# ws2812-cube-reverse.net
KiCad netlist of a schematic drawn in EasyEDA
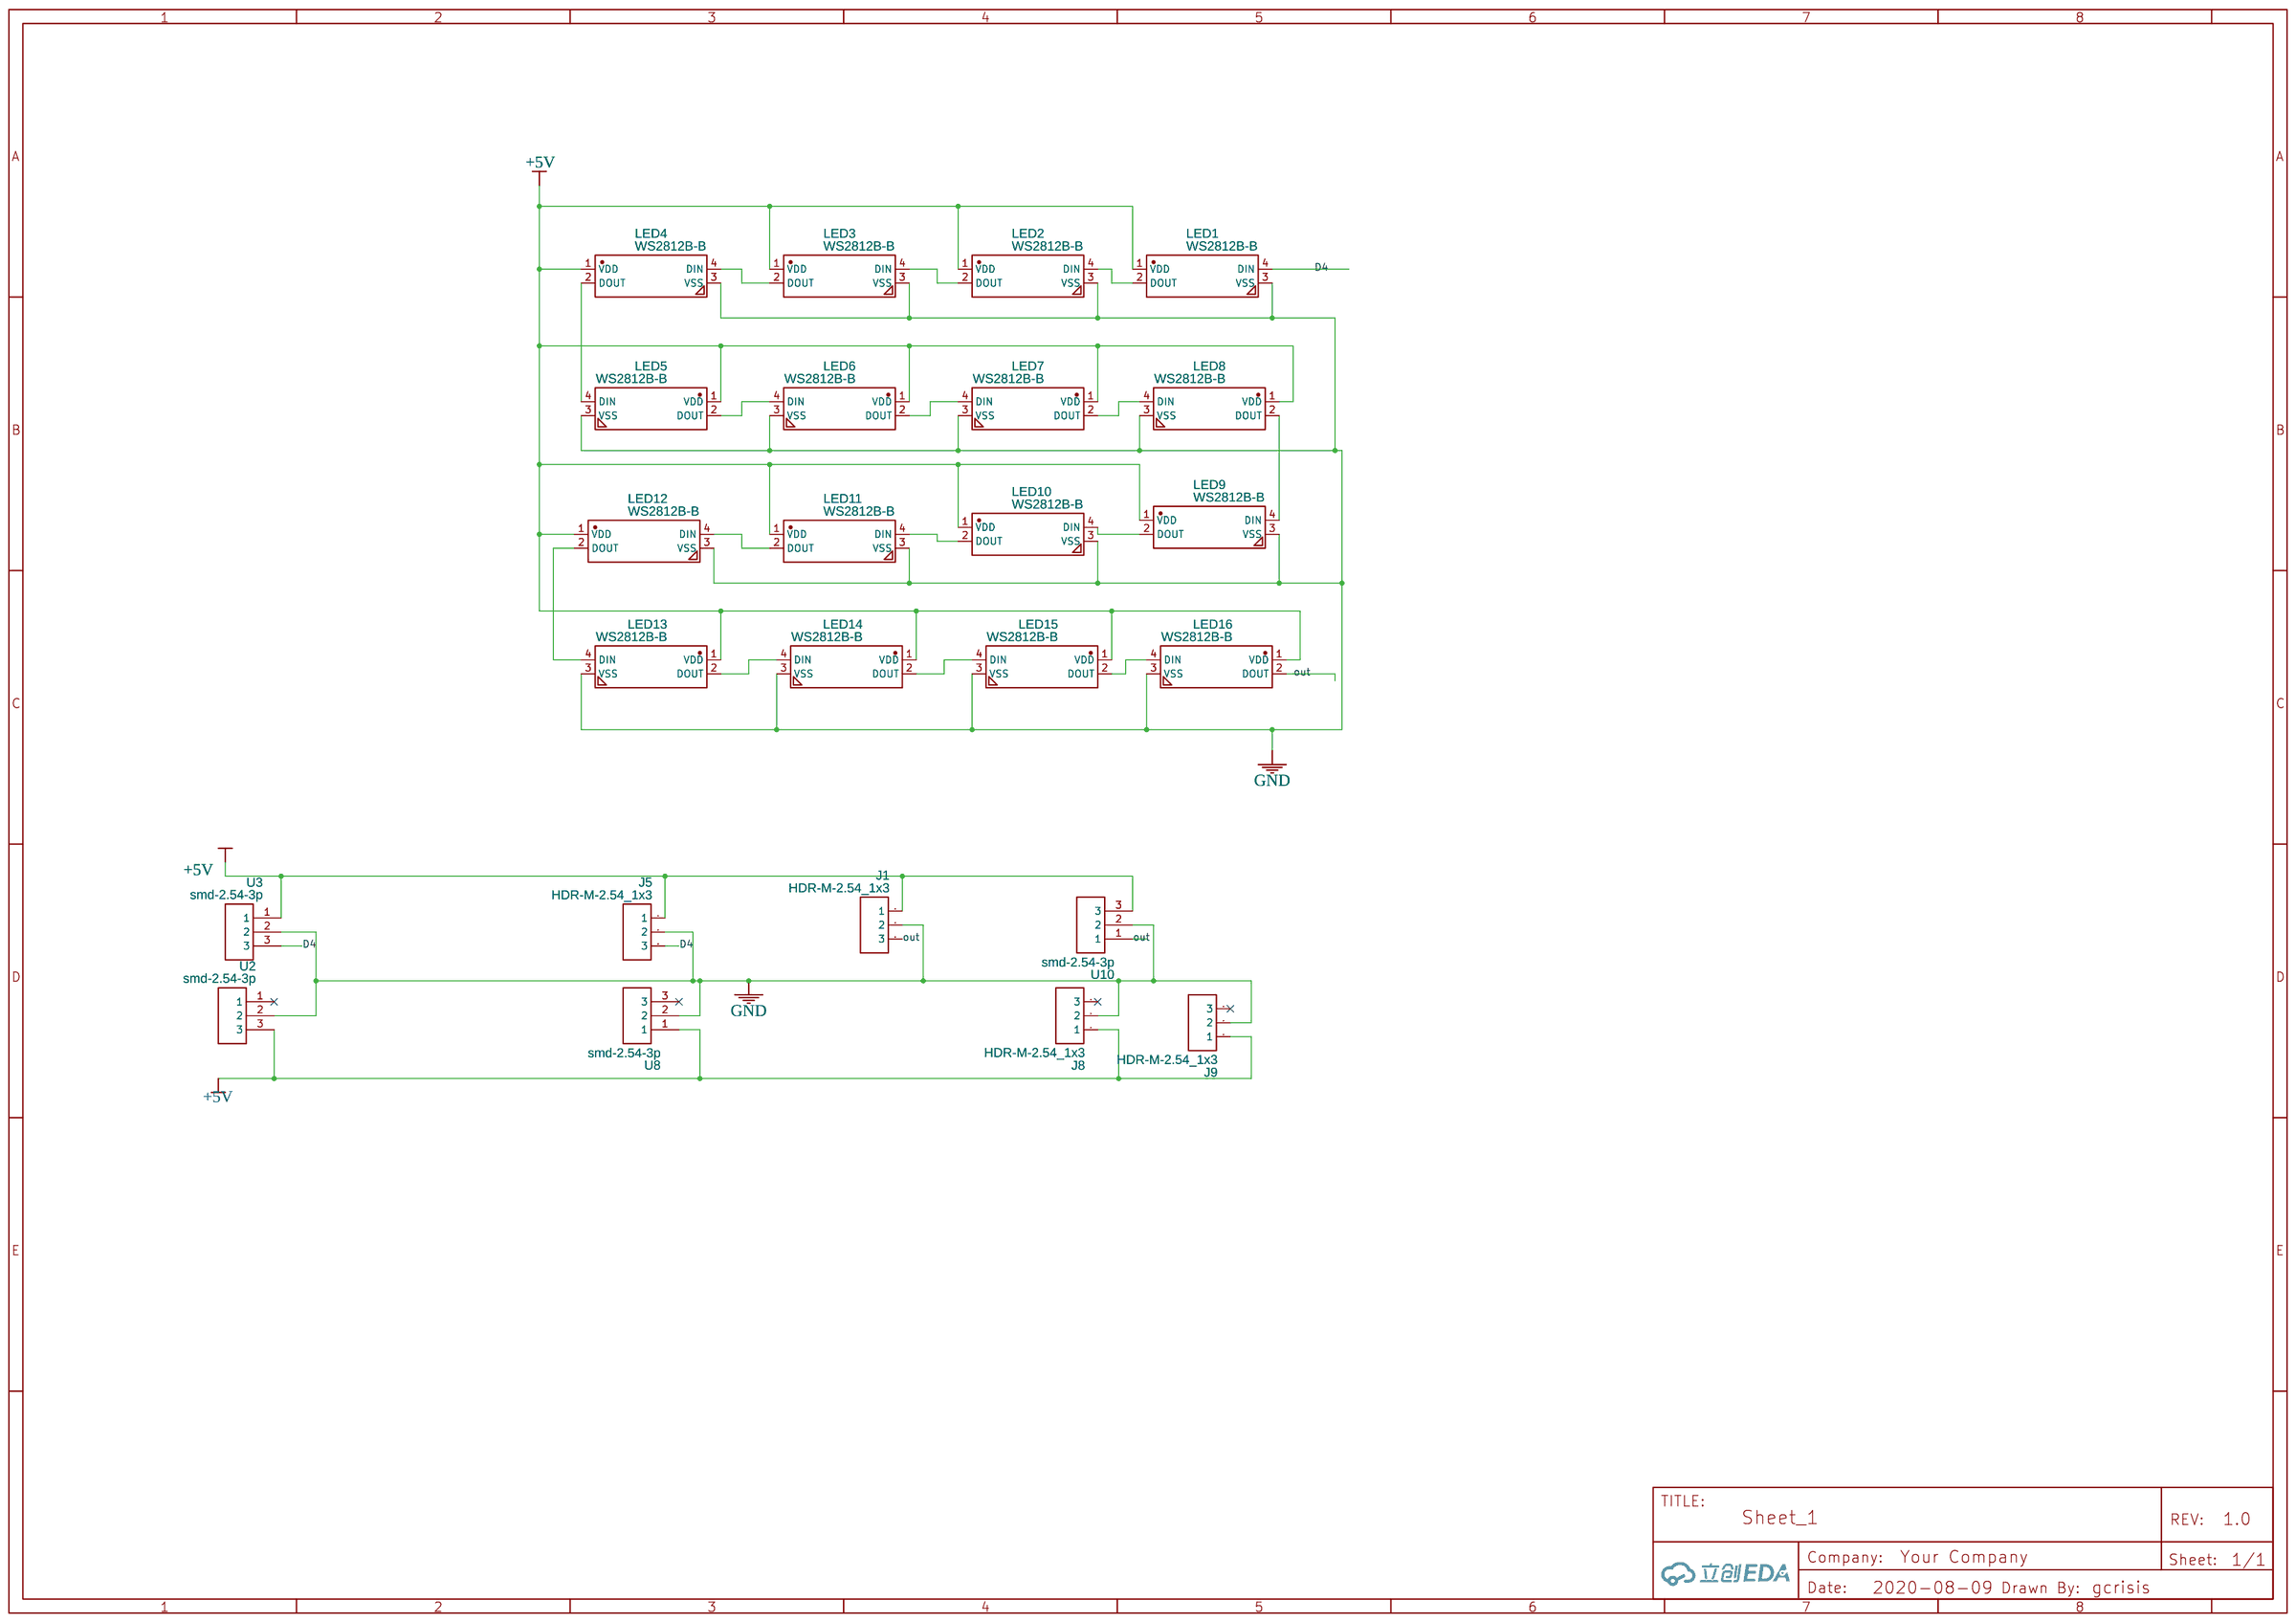
[diagram p0: schematic sheet]

(export (version "E")
  (design (tool "Eeschema 10.0.6"))
  (components
    (comp (ref "J1")
      (value "HDR-M-2.54_1x3")
      (fields (field (name "BOM_Supplier Part") "C180248"))
      (libsource (lib "") (part "HDR-M-2.54_1x3_1"))
    )
    (comp (ref "J5")
      (value "HDR-M-2.54_1x3")
      (fields (field (name "BOM_Supplier Part") "C180248"))
      (libsource (lib "") (part "HDR-M-2.54_1x3_1"))
    )
    (comp (ref "J8")
      (value "HDR-M-2.54_1x3")
      (fields (field (name "BOM_Supplier Part") "C180248"))
      (libsource (lib "") (part "HDR-M-2.54_1x3"))
    )
    (comp (ref "J9")
      (value "HDR-M-2.54_1x3")
      (fields (field (name "BOM_Supplier Part") "C180248"))
      (libsource (lib "") (part "HDR-M-2.54_1x3"))
    )
    (comp (ref "LED1")
      (value "WS2812B-B")
      (fields (field (name "BOM_Supplier Part") "C114586"))
      (libsource (lib "") (part "WS2812B-B"))
    )
    (comp (ref "LED2")
      (value "WS2812B-B")
      (fields (field (name "BOM_Supplier Part") "C114586"))
      (libsource (lib "") (part "WS2812B-B"))
    )
    (comp (ref "LED3")
      (value "WS2812B-B")
      (fields (field (name "BOM_Supplier Part") "C114586"))
      (libsource (lib "") (part "WS2812B-B"))
    )
    (comp (ref "LED4")
      (value "WS2812B-B")
      (fields (field (name "BOM_Supplier Part") "C114586"))
      (libsource (lib "") (part "WS2812B-B"))
    )
    (comp (ref "LED5")
      (value "WS2812B-B")
      (fields (field (name "BOM_Supplier Part") "C114586"))
      (libsource (lib "") (part "WS2812B-B_1"))
    )
    (comp (ref "LED6")
      (value "WS2812B-B")
      (fields (field (name "BOM_Supplier Part") "C114586"))
      (libsource (lib "") (part "WS2812B-B_1"))
    )
    (comp (ref "LED7")
      (value "WS2812B-B")
      (fields (field (name "BOM_Supplier Part") "C114586"))
      (libsource (lib "") (part "WS2812B-B_1"))
    )
    (comp (ref "LED8")
      (value "WS2812B-B")
      (fields (field (name "BOM_Supplier Part") "C114586"))
      (libsource (lib "") (part "WS2812B-B_1"))
    )
    (comp (ref "LED9")
      (value "WS2812B-B")
      (fields (field (name "BOM_Supplier Part") "C114586"))
      (libsource (lib "") (part "WS2812B-B"))
    )
    (comp (ref "LED10")
      (value "WS2812B-B")
      (fields (field (name "BOM_Supplier Part") "C114586"))
      (libsource (lib "") (part "WS2812B-B"))
    )
    (comp (ref "LED11")
      (value "WS2812B-B")
      (fields (field (name "BOM_Supplier Part") "C114586"))
      (libsource (lib "") (part "WS2812B-B"))
    )
    (comp (ref "LED12")
      (value "WS2812B-B")
      (fields (field (name "BOM_Supplier Part") "C114586"))
      (libsource (lib "") (part "WS2812B-B"))
    )
    (comp (ref "LED13")
      (value "WS2812B-B")
      (fields (field (name "BOM_Supplier Part") "C114586"))
      (libsource (lib "") (part "WS2812B-B_1"))
    )
    (comp (ref "LED14")
      (value "WS2812B-B")
      (fields (field (name "BOM_Supplier Part") "C114586"))
      (libsource (lib "") (part "WS2812B-B_1"))
    )
    (comp (ref "LED15")
      (value "WS2812B-B")
      (fields (field (name "BOM_Supplier Part") "C114586"))
      (libsource (lib "") (part "WS2812B-B_1"))
    )
    (comp (ref "LED16")
      (value "WS2812B-B")
      (fields (field (name "BOM_Supplier Part") "C114586"))
      (libsource (lib "") (part "WS2812B-B_1"))
    )
    (comp (ref "U2") (value "smd-2.54-3p") (libsource (lib "") (part "smd-2.54-3p_1")))
    (comp (ref "U3") (value "smd-2.54-3p") (libsource (lib "") (part "smd-2.54-3p_1")))
    (comp (ref "U8") (value "smd-2.54-3p") (libsource (lib "") (part "smd-2.54-3p")))
    (comp (ref "U10") (value "smd-2.54-3p") (libsource (lib "") (part "smd-2.54-3p")))
  )
  (nets
    (net (code "1") (name "+5V") (class "Default")
      (node (ref "J1") (pin "1") (pinfunction "1_1") (pintype "input"))
      (node (ref "J5") (pin "1") (pinfunction "1_1") (pintype "input"))
      (node (ref "J8") (pin "1") (pinfunction "1_1") (pintype "input"))
      (node (ref "J9") (pin "1") (pinfunction "1_1") (pintype "input"))
      (node (ref "LED1") (pin "1") (pinfunction "VDD_1") (pintype "unspecified"))
      (node (ref "LED10") (pin "1") (pinfunction "VDD_1") (pintype "unspecified"))
      (node (ref "LED11") (pin "1") (pinfunction "VDD_1") (pintype "unspecified"))
      (node (ref "LED12") (pin "1") (pinfunction "VDD_1") (pintype "unspecified"))
      (node (ref "LED13") (pin "1") (pinfunction "VDD_1") (pintype "unspecified"))
      (node (ref "LED14") (pin "1") (pinfunction "VDD_1") (pintype "unspecified"))
      (node (ref "LED15") (pin "1") (pinfunction "VDD_1") (pintype "unspecified"))
      (node (ref "LED16") (pin "1") (pinfunction "VDD_1") (pintype "unspecified"))
      (node (ref "LED2") (pin "1") (pinfunction "VDD_1") (pintype "unspecified"))
      (node (ref "LED3") (pin "1") (pinfunction "VDD_1") (pintype "unspecified"))
      (node (ref "LED4") (pin "1") (pinfunction "VDD_1") (pintype "unspecified"))
      (node (ref "LED5") (pin "1") (pinfunction "VDD_1") (pintype "unspecified"))
      (node (ref "LED6") (pin "1") (pinfunction "VDD_1") (pintype "unspecified"))
      (node (ref "LED7") (pin "1") (pinfunction "VDD_1") (pintype "unspecified"))
      (node (ref "LED8") (pin "1") (pinfunction "VDD_1") (pintype "unspecified"))
      (node (ref "LED9") (pin "1") (pinfunction "VDD_1") (pintype "unspecified"))
      (node (ref "U10") (pin "3") (pinfunction "3_3") (pintype "unspecified"))
      (node (ref "U2") (pin "3") (pinfunction "3_3") (pintype "unspecified"))
      (node (ref "U3") (pin "1") (pinfunction "1_1") (pintype "unspecified"))
      (node (ref "U8") (pin "1") (pinfunction "1_1") (pintype "unspecified"))
    )
    (net (code "2") (name "/D4") (class "Default")
      (node (ref "J5") (pin "3") (pinfunction "3_3") (pintype "input"))
      (node (ref "LED1") (pin "4") (pinfunction "DIN_4") (pintype "unspecified"))
      (node (ref "U3") (pin "3") (pinfunction "3_3") (pintype "unspecified"))
    )
    (net (code "3") (name "/out") (class "Default")
      (node (ref "J1") (pin "3") (pinfunction "3_3") (pintype "input"))
      (node (ref "LED16") (pin "2") (pinfunction "DOUT_2") (pintype "unspecified"))
      (node (ref "U10") (pin "1") (pinfunction "1_1") (pintype "unspecified"))
    )
    (net (code "4") (name "GND") (class "Default")
      (node (ref "J1") (pin "2") (pinfunction "2_2") (pintype "input"))
      (node (ref "J5") (pin "2") (pinfunction "2_2") (pintype "input"))
      (node (ref "J8") (pin "2") (pinfunction "2_2") (pintype "input"))
      (node (ref "J9") (pin "2") (pinfunction "2_2") (pintype "input"))
      (node (ref "LED1") (pin "3") (pinfunction "VSS_3") (pintype "unspecified"))
      (node (ref "LED10") (pin "3") (pinfunction "VSS_3") (pintype "unspecified"))
      (node (ref "LED11") (pin "3") (pinfunction "VSS_3") (pintype "unspecified"))
      (node (ref "LED12") (pin "3") (pinfunction "VSS_3") (pintype "unspecified"))
      (node (ref "LED13") (pin "3") (pinfunction "VSS_3") (pintype "unspecified"))
      (node (ref "LED14") (pin "3") (pinfunction "VSS_3") (pintype "unspecified"))
      (node (ref "LED15") (pin "3") (pinfunction "VSS_3") (pintype "unspecified"))
      (node (ref "LED16") (pin "3") (pinfunction "VSS_3") (pintype "unspecified"))
      (node (ref "LED2") (pin "3") (pinfunction "VSS_3") (pintype "unspecified"))
      (node (ref "LED3") (pin "3") (pinfunction "VSS_3") (pintype "unspecified"))
      (node (ref "LED4") (pin "3") (pinfunction "VSS_3") (pintype "unspecified"))
      (node (ref "LED5") (pin "3") (pinfunction "VSS_3") (pintype "unspecified"))
      (node (ref "LED6") (pin "3") (pinfunction "VSS_3") (pintype "unspecified"))
      (node (ref "LED7") (pin "3") (pinfunction "VSS_3") (pintype "unspecified"))
      (node (ref "LED8") (pin "3") (pinfunction "VSS_3") (pintype "unspecified"))
      (node (ref "LED9") (pin "3") (pinfunction "VSS_3") (pintype "unspecified"))
      (node (ref "U10") (pin "2") (pinfunction "2_2") (pintype "unspecified"))
      (node (ref "U2") (pin "2") (pinfunction "2_2") (pintype "unspecified"))
      (node (ref "U3") (pin "2") (pinfunction "2_2") (pintype "unspecified"))
      (node (ref "U8") (pin "2") (pinfunction "2_2") (pintype "unspecified"))
    )
    (net (code "5") (name "Net-(LED1-DOUT)") (class "Default")
      (node (ref "LED1") (pin "2") (pinfunction "DOUT_2") (pintype "unspecified"))
      (node (ref "LED2") (pin "4") (pinfunction "DIN_4") (pintype "unspecified"))
    )
    (net (code "6") (name "Net-(LED2-DOUT)") (class "Default")
      (node (ref "LED2") (pin "2") (pinfunction "DOUT_2") (pintype "unspecified"))
      (node (ref "LED3") (pin "4") (pinfunction "DIN_4") (pintype "unspecified"))
    )
    (net (code "7") (name "Net-(LED3-DOUT)") (class "Default")
      (node (ref "LED3") (pin "2") (pinfunction "DOUT_2") (pintype "unspecified"))
      (node (ref "LED4") (pin "4") (pinfunction "DIN_4") (pintype "unspecified"))
    )
    (net (code "8") (name "Net-(LED4-DOUT)") (class "Default")
      (node (ref "LED4") (pin "2") (pinfunction "DOUT_2") (pintype "unspecified"))
      (node (ref "LED5") (pin "4") (pinfunction "DIN_4") (pintype "unspecified"))
    )
    (net (code "9") (name "Net-(LED5-DOUT)") (class "Default")
      (node (ref "LED5") (pin "2") (pinfunction "DOUT_2") (pintype "unspecified"))
      (node (ref "LED6") (pin "4") (pinfunction "DIN_4") (pintype "unspecified"))
    )
    (net (code "10") (name "Net-(LED6-DOUT)") (class "Default")
      (node (ref "LED6") (pin "2") (pinfunction "DOUT_2") (pintype "unspecified"))
      (node (ref "LED7") (pin "4") (pinfunction "DIN_4") (pintype "unspecified"))
    )
    (net (code "11") (name "Net-(LED7-DOUT)") (class "Default")
      (node (ref "LED7") (pin "2") (pinfunction "DOUT_2") (pintype "unspecified"))
      (node (ref "LED8") (pin "4") (pinfunction "DIN_4") (pintype "unspecified"))
    )
    (net (code "12") (name "Net-(LED8-DOUT)") (class "Default")
      (node (ref "LED8") (pin "2") (pinfunction "DOUT_2") (pintype "unspecified"))
      (node (ref "LED9") (pin "4") (pinfunction "DIN_4") (pintype "unspecified"))
    )
    (net (code "13") (name "Net-(LED10-DIN)") (class "Default")
      (node (ref "LED10") (pin "4") (pinfunction "DIN_4") (pintype "unspecified"))
      (node (ref "LED9") (pin "2") (pinfunction "DOUT_2") (pintype "unspecified"))
    )
    (net (code "14") (name "Net-(LED10-DOUT)") (class "Default")
      (node (ref "LED10") (pin "2") (pinfunction "DOUT_2") (pintype "unspecified"))
      (node (ref "LED11") (pin "4") (pinfunction "DIN_4") (pintype "unspecified"))
    )
    (net (code "15") (name "Net-(LED11-DOUT)") (class "Default")
      (node (ref "LED11") (pin "2") (pinfunction "DOUT_2") (pintype "unspecified"))
      (node (ref "LED12") (pin "4") (pinfunction "DIN_4") (pintype "unspecified"))
    )
    (net (code "16") (name "Net-(LED12-DOUT)") (class "Default")
      (node (ref "LED12") (pin "2") (pinfunction "DOUT_2") (pintype "unspecified"))
      (node (ref "LED13") (pin "4") (pinfunction "DIN_4") (pintype "unspecified"))
    )
    (net (code "17") (name "Net-(LED13-DOUT)") (class "Default")
      (node (ref "LED13") (pin "2") (pinfunction "DOUT_2") (pintype "unspecified"))
      (node (ref "LED14") (pin "4") (pinfunction "DIN_4") (pintype "unspecified"))
    )
    (net (code "18") (name "Net-(LED14-DOUT)") (class "Default")
      (node (ref "LED14") (pin "2") (pinfunction "DOUT_2") (pintype "unspecified"))
      (node (ref "LED15") (pin "4") (pinfunction "DIN_4") (pintype "unspecified"))
    )
    (net (code "19") (name "Net-(LED15-DOUT)") (class "Default")
      (node (ref "LED15") (pin "2") (pinfunction "DOUT_2") (pintype "unspecified"))
      (node (ref "LED16") (pin "4") (pinfunction "DIN_4") (pintype "unspecified"))
    )
    (net (code "20") (name "unconnected-(J8-Pad3)") (class "Default")
      (node (ref "J8") (pin "3") (pinfunction "3_3") (pintype "input+no_connect"))
    )
    (net (code "21") (name "unconnected-(J9-Pad3)") (class "Default")
      (node (ref "J9") (pin "3") (pinfunction "3_3") (pintype "input+no_connect"))
    )
    (net (code "22") (name "unconnected-(U2-Pad1)") (class "Default")
      (node (ref "U2") (pin "1") (pinfunction "1_1") (pintype "unspecified+no_connect"))
    )
    (net (code "23") (name "unconnected-(U8-Pad3)") (class "Default")
      (node (ref "U8") (pin "3") (pinfunction "3_3") (pintype "unspecified+no_connect"))
    )
  )
)
